# Haptic.net
KiCad netlist of a schematic drawn in EAGLE
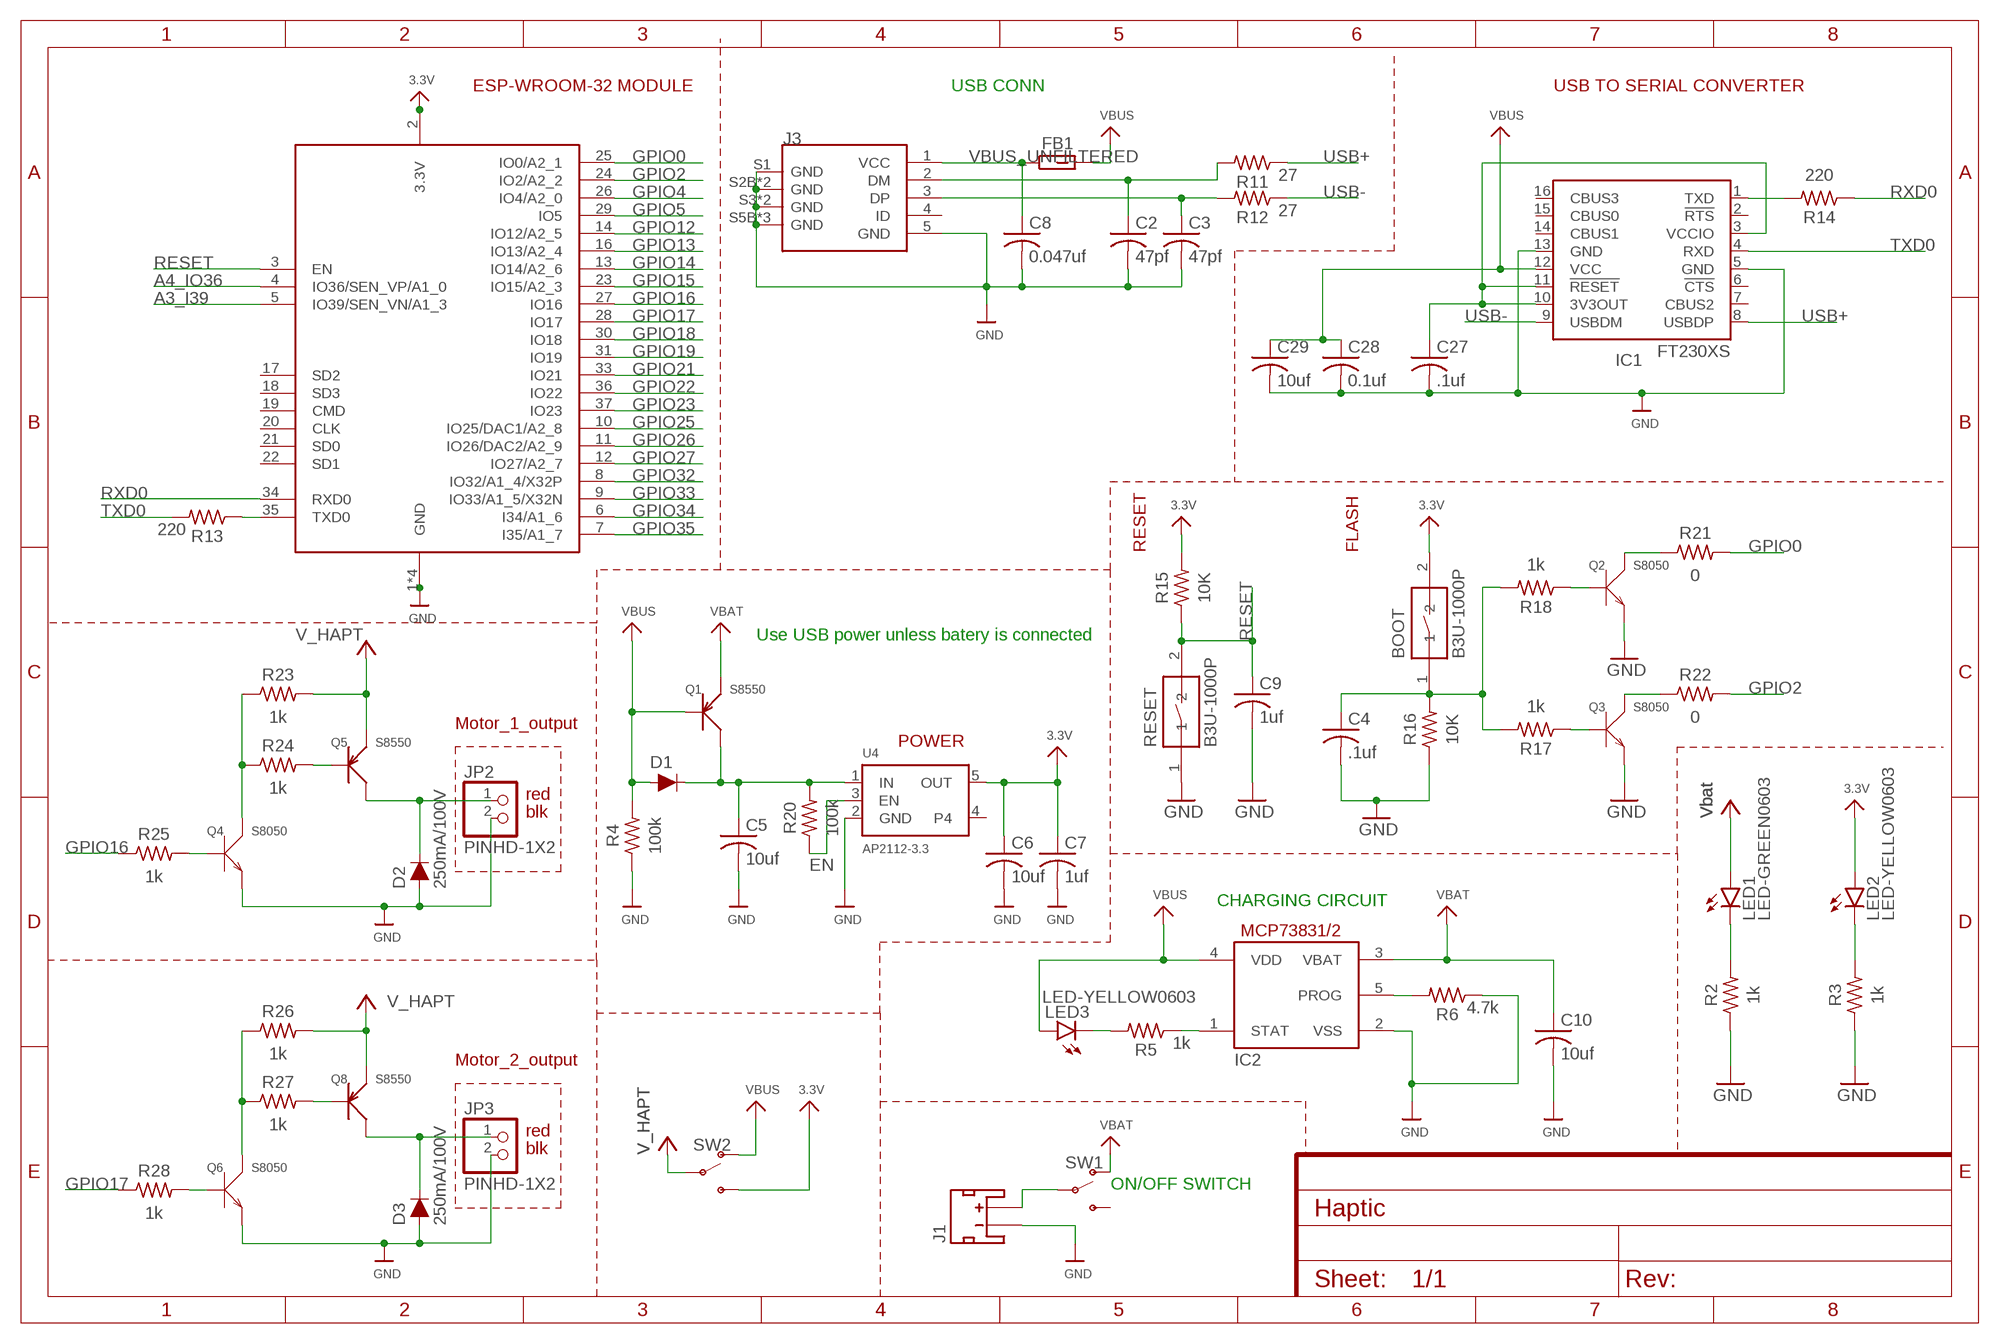
[diagram p0: schematic, sheet 1]

(export (version "E")
  (design (tool "Eeschema 10.0.6"))
  (components
    (comp (ref "BOOT")
      (value "B3U-1000P")
      (footprint "eagle-import:B3U-1000P")
      (fields
        (field (name "DIGI_KEY_PART_NUMBER") "SW1020CT-ND")
        (field (name "MANUFACTURER") "Omron Electronics Inc-EMC Div")
        (field (name "CREATED_BY") "PCBLayout.com")
      )
      (libsource (lib "eagle-import") (part "B3U-1000P"))
    )
    (comp (ref "C2")
      (value "47pf")
      (footprint "eagle-import:CAPC1608X85")
      (libsource (lib "eagle-import") (part "C-USCHIP-0603(1608-METRIC)_"))
    )
    (comp (ref "C3")
      (value "47pf")
      (footprint "eagle-import:CAPC1608X85")
      (libsource (lib "eagle-import") (part "C-USCHIP-0603(1608-METRIC)_"))
    )
    (comp (ref "C4")
      (value ".1uf")
      (footprint "eagle-import:CAPC1608X85")
      (libsource (lib "eagle-import") (part "C-USCHIP-0603(1608-METRIC)_"))
    )
    (comp (ref "C5")
      (value "10uf")
      (footprint "eagle-import:CAPC1608X85")
      (libsource (lib "eagle-import") (part "C-USCHIP-0603(1608-METRIC)_"))
    )
    (comp (ref "C6")
      (value "10uf")
      (footprint "eagle-import:CAPC1608X85")
      (libsource (lib "eagle-import") (part "C-USCHIP-0603(1608-METRIC)_"))
    )
    (comp (ref "C7")
      (value "1uf")
      (footprint "eagle-import:CAPC1608X85")
      (libsource (lib "eagle-import") (part "C-USCHIP-0603(1608-METRIC)_"))
    )
    (comp (ref "C8")
      (value "0.047uf")
      (footprint "eagle-import:CAPC1608X85")
      (libsource (lib "eagle-import") (part "C-USCHIP-0603(1608-METRIC)_"))
    )
    (comp (ref "C9")
      (value "1uf")
      (footprint "eagle-import:CAPC1608X85")
      (libsource (lib "eagle-import") (part "C-USCHIP-0603(1608-METRIC)_"))
    )
    (comp (ref "C10")
      (value "10uf")
      (footprint "eagle-import:CAPC1608X85")
      (libsource (lib "eagle-import") (part "C-USCHIP-0603(1608-METRIC)_"))
    )
    (comp (ref "C27")
      (value ".1uf")
      (footprint "eagle-import:CAPC1608X85")
      (libsource (lib "eagle-import") (part "C-USCHIP-0603(1608-METRIC)_"))
    )
    (comp (ref "C28")
      (value "0.1uf")
      (footprint "eagle-import:CAPC1608X85")
      (libsource (lib "eagle-import") (part "C-USCHIP-0603(1608-METRIC)_"))
    )
    (comp (ref "C29")
      (value "10uf")
      (footprint "eagle-import:CAPC1608X85")
      (libsource (lib "eagle-import") (part "C-USCHIP-0603(1608-METRIC)_"))
    )
    (comp (ref "D1")
      (value "250mA/100V")
      (footprint "eagle-import:SOD-323")
      (libsource (lib "eagle-import") (part "DIODE-BAS16J"))
    )
    (comp (ref "D2")
      (value "250mA/100V")
      (footprint "eagle-import:SOD-323")
      (libsource (lib "eagle-import") (part "DIODE-BAS16J"))
    )
    (comp (ref "D3")
      (value "250mA/100V")
      (footprint "eagle-import:SOD-323")
      (libsource (lib "eagle-import") (part "DIODE-BAS16J"))
    )
    (comp (ref "FB1")
      (value "BK1608TS601-T")
      (footprint "eagle-import:BEADC1608X95N")
      (libsource (lib "eagle-import") (part "FBCHIP-0603(1608-METRIC)"))
    )
    (comp (ref "IC1")
      (value "FT230XS")
      (footprint "eagle-import:SSOP16")
      (libsource (lib "eagle-import") (part "FT230XS"))
    )
    (comp (ref "IC2")
      (value "MCP73831/OT")
      (footprint "eagle-import:SOT23-5L")
      (libsource (lib "eagle-import") (part "MCP73831/OT"))
    )
    (comp (ref "J1")
      (value "JST_2MM_MALE")
      (footprint "eagle-import:JST-2-SMD")
      (libsource (lib "eagle-import") (part "JST_2MM_MALE"))
    )
    (comp (ref "J3")
      (value "10118193-0001LF")
      (footprint "eagle-import:MICRO-USB5+6P-SMD-0.65-B")
      (libsource (lib "eagle-import") (part "MICRO-USB-SMD-B-(10118193-0001LF)"))
    )
    (comp (ref "JP2")
      (value "PINHD-1X2")
      (footprint "eagle-import:1X02")
      (libsource (lib "eagle-import") (part "PINHD-1X2"))
    )
    (comp (ref "JP3")
      (value "PINHD-1X2")
      (footprint "eagle-import:1X02")
      (libsource (lib "eagle-import") (part "PINHD-1X2"))
    )
    (comp (ref "LED1")
      (value "LED-GREEN0603")
      (footprint "eagle-import:0603-GREEN")
      (libsource (lib "eagle-import") (part "LED-GREEN0603"))
    )
    (comp (ref "LED2")
      (value "LED-YELLOW0603")
      (footprint "eagle-import:0603-YELLOW")
      (libsource (lib "eagle-import") (part "LED-YELLOW0603"))
    )
    (comp (ref "LED3")
      (value "LED-YELLOW0603")
      (footprint "eagle-import:0603-YELLOW")
      (libsource (lib "eagle-import") (part "LED-YELLOW0603"))
    )
    (comp (ref "Q1")
      (value "S8550")
      (footprint "eagle-import:SOT-23")
      (libsource (lib "eagle-import") (part "SMD-TRANSISTORS-PNP-25V-500MA-S8550(SOT-23)"))
    )
    (comp (ref "Q2")
      (value "S8050")
      (footprint "eagle-import:SOT-23")
      (libsource (lib "eagle-import") (part "SMD-TRANSISTORS-NPN-25V-500MW-S8050(SOT-23)"))
    )
    (comp (ref "Q3")
      (value "S8050")
      (footprint "eagle-import:SOT-23")
      (libsource (lib "eagle-import") (part "SMD-TRANSISTORS-NPN-25V-500MW-S8050(SOT-23)"))
    )
    (comp (ref "Q4")
      (value "S8050")
      (footprint "eagle-import:SOT-23")
      (libsource (lib "eagle-import") (part "SMD-TRANSISTORS-NPN-25V-500MW-S8050(SOT-23)"))
    )
    (comp (ref "Q5")
      (value "S8550")
      (footprint "eagle-import:SOT-23")
      (libsource (lib "eagle-import") (part "SMD-TRANSISTORS-PNP-25V-500MA-S8550(SOT-23)"))
    )
    (comp (ref "Q6")
      (value "S8050")
      (footprint "eagle-import:SOT-23")
      (libsource (lib "eagle-import") (part "SMD-TRANSISTORS-NPN-25V-500MW-S8050(SOT-23)"))
    )
    (comp (ref "Q8")
      (value "S8550")
      (footprint "eagle-import:SOT-23")
      (libsource (lib "eagle-import") (part "SMD-TRANSISTORS-PNP-25V-500MA-S8550(SOT-23)"))
    )
    (comp (ref "R2")
      (value "1k")
      (footprint "eagle-import:RESC1608X60")
      (libsource (lib "eagle-import") (part "R-USCHIP-0603(1608-METRIC)_"))
    )
    (comp (ref "R3")
      (value "1k")
      (footprint "eagle-import:RESC1608X60")
      (libsource (lib "eagle-import") (part "R-USCHIP-0603(1608-METRIC)_"))
    )
    (comp (ref "R4")
      (value "100k")
      (footprint "eagle-import:RESC1608X60")
      (libsource (lib "eagle-import") (part "R-USCHIP-0603(1608-METRIC)_"))
    )
    (comp (ref "R5")
      (value "1k")
      (footprint "eagle-import:RESC1608X60")
      (libsource (lib "eagle-import") (part "R-USCHIP-0603(1608-METRIC)_"))
    )
    (comp (ref "R6")
      (value "4.7k")
      (footprint "eagle-import:RESC1608X60")
      (libsource (lib "eagle-import") (part "R-USCHIP-0603(1608-METRIC)_"))
    )
    (comp (ref "R11")
      (value "27")
      (footprint "eagle-import:RESC1608X60")
      (libsource (lib "eagle-import") (part "R-USCHIP-0603(1608-METRIC)_"))
    )
    (comp (ref "R12")
      (value "27")
      (footprint "eagle-import:RESC1608X60")
      (libsource (lib "eagle-import") (part "R-USCHIP-0603(1608-METRIC)_"))
    )
    (comp (ref "R13")
      (value "220")
      (footprint "eagle-import:RESC1608X60")
      (libsource (lib "eagle-import") (part "R-USCHIP-0603(1608-METRIC)_"))
    )
    (comp (ref "R14")
      (value "220")
      (footprint "eagle-import:RESC1608X60")
      (libsource (lib "eagle-import") (part "R-USCHIP-0603(1608-METRIC)_"))
    )
    (comp (ref "R15")
      (value "10K")
      (footprint "eagle-import:RESC1608X60")
      (libsource (lib "eagle-import") (part "R-USCHIP-0603(1608-METRIC)_"))
    )
    (comp (ref "R16")
      (value "10K")
      (footprint "eagle-import:RESC1608X60")
      (libsource (lib "eagle-import") (part "R-USCHIP-0603(1608-METRIC)_"))
    )
    (comp (ref "R17")
      (value "1k")
      (footprint "eagle-import:RESC1608X60")
      (libsource (lib "eagle-import") (part "R-USCHIP-0603(1608-METRIC)_"))
    )
    (comp (ref "R18")
      (value "1k")
      (footprint "eagle-import:RESC1608X60")
      (libsource (lib "eagle-import") (part "R-USCHIP-0603(1608-METRIC)_"))
    )
    (comp (ref "R20")
      (value "100k")
      (footprint "eagle-import:RESC1608X60")
      (libsource (lib "eagle-import") (part "R-USCHIP-0603(1608-METRIC)_"))
    )
    (comp (ref "R21")
      (value "0")
      (footprint "eagle-import:RESC1608X60")
      (libsource (lib "eagle-import") (part "R-USCHIP-0603(1608-METRIC)_"))
    )
    (comp (ref "R22")
      (value "0")
      (footprint "eagle-import:RESC1608X60")
      (libsource (lib "eagle-import") (part "R-USCHIP-0603(1608-METRIC)_"))
    )
    (comp (ref "R23")
      (value "1k")
      (footprint "eagle-import:RESC1608X60")
      (libsource (lib "eagle-import") (part "R-USCHIP-0603(1608-METRIC)_"))
    )
    (comp (ref "R24")
      (value "1k")
      (footprint "eagle-import:RESC1608X60")
      (libsource (lib "eagle-import") (part "R-USCHIP-0603(1608-METRIC)_"))
    )
    (comp (ref "R25")
      (value "1k")
      (footprint "eagle-import:RESC1608X60")
      (libsource (lib "eagle-import") (part "R-USCHIP-0603(1608-METRIC)_"))
    )
    (comp (ref "R26")
      (value "1k")
      (footprint "eagle-import:RESC1608X60")
      (libsource (lib "eagle-import") (part "R-USCHIP-0603(1608-METRIC)_"))
    )
    (comp (ref "R27")
      (value "1k")
      (footprint "eagle-import:RESC1608X60")
      (libsource (lib "eagle-import") (part "R-USCHIP-0603(1608-METRIC)_"))
    )
    (comp (ref "R28")
      (value "1k")
      (footprint "eagle-import:RESC1608X60")
      (libsource (lib "eagle-import") (part "R-USCHIP-0603(1608-METRIC)_"))
    )
    (comp (ref "RESET")
      (value "B3U-1000P")
      (footprint "eagle-import:B3U-1000P")
      (fields
        (field (name "DIGI_KEY_PART_NUMBER") "SW1020CT-ND")
        (field (name "MANUFACTURER") "Omron Electronics Inc-EMC Div")
        (field (name "CREATED_BY") "PCBLayout.com")
      )
      (libsource (lib "eagle-import") (part "B3U-1000P"))
    )
    (comp (ref "SW1")
      (value "SWITCH-SPDT-SMD-RIGHT-ANGLE")
      (footprint "eagle-import:SWITCH_SPST_SMD_A")
      (libsource (lib "eagle-import") (part "SWITCH-SPDT-SMD-RIGHT-ANGLE"))
    )
    (comp (ref "SW2")
      (value "SWITCH-SPDT-SMD-RIGHT-ANGLE")
      (footprint "eagle-import:SWITCH_SPST_SMD_A")
      (libsource (lib "eagle-import") (part "SWITCH-SPDT-SMD-RIGHT-ANGLE"))
    )
    (comp (ref "U4")
      (value "AP2112-3.3")
      (footprint "eagle-import:SOT23-5")
      (libsource (lib "eagle-import") (part "VREG_SOT23-5"))
    )
    (comp (ref "X6")
      (value "ESP32_WROOM32_SKINNY")
      (footprint "eagle-import:WROOM32_SKINNY")
      (libsource (lib "eagle-import") (part "ESP32_WROOM32_SKINNY"))
    )
  )
  (nets
    (net (code "1") (name "/A3_I39") (class "Default")
      (node (ref "X6") (pin "5") (pinfunction "IO39/SEN_VN/A1_3_5") (pintype "passive"))
    )
    (net (code "2") (name "/A4_IO36") (class "Default")
      (node (ref "X6") (pin "4") (pinfunction "IO36/SEN_VP/A1_0_4") (pintype "passive"))
    )
    (net (code "3") (name "/EN") (class "Default")
      (node (ref "R20") (pin "1") (pinfunction "1_1") (pintype "passive"))
      (node (ref "U4") (pin "3") (pinfunction "EN_3") (pintype "input"))
    )
    (net (code "4") (name "/GPIO0") (class "Default")
      (node (ref "R21") (pin "2") (pinfunction "2_2") (pintype "passive"))
      (node (ref "X6") (pin "25") (pinfunction "IO0/A2_1_25") (pintype "bidirectional"))
    )
    (net (code "5") (name "/GPIO2") (class "Default")
      (node (ref "R22") (pin "2") (pinfunction "2_2") (pintype "passive"))
      (node (ref "X6") (pin "24") (pinfunction "IO2/A2_2_24") (pintype "bidirectional"))
    )
    (net (code "6") (name "/GPIO4") (class "Default")
      (node (ref "X6") (pin "26") (pinfunction "IO4/A2_0_26") (pintype "bidirectional"))
    )
    (net (code "7") (name "/GPIO5") (class "Default")
      (node (ref "X6") (pin "29") (pinfunction "IO5_29") (pintype "bidirectional"))
    )
    (net (code "8") (name "/GPIO12") (class "Default")
      (node (ref "X6") (pin "14") (pinfunction "IO12/A2_5_14") (pintype "bidirectional"))
    )
    (net (code "9") (name "/GPIO13") (class "Default")
      (node (ref "X6") (pin "16") (pinfunction "IO13/A2_4_16") (pintype "bidirectional"))
    )
    (net (code "10") (name "/GPIO14") (class "Default")
      (node (ref "X6") (pin "13") (pinfunction "IO14/A2_6_13") (pintype "bidirectional"))
    )
    (net (code "11") (name "/GPIO15") (class "Default")
      (node (ref "X6") (pin "23") (pinfunction "IO15/A2_3_23") (pintype "bidirectional"))
    )
    (net (code "12") (name "/GPIO16") (class "Default")
      (node (ref "R25") (pin "1") (pinfunction "1_1") (pintype "passive"))
      (node (ref "X6") (pin "27") (pinfunction "IO16_27") (pintype "bidirectional"))
    )
    (net (code "13") (name "/GPIO17") (class "Default")
      (node (ref "R28") (pin "1") (pinfunction "1_1") (pintype "passive"))
      (node (ref "X6") (pin "28") (pinfunction "IO17_28") (pintype "bidirectional"))
    )
    (net (code "14") (name "/GPIO18") (class "Default")
      (node (ref "X6") (pin "30") (pinfunction "IO18_30") (pintype "bidirectional"))
    )
    (net (code "15") (name "/GPIO19") (class "Default")
      (node (ref "X6") (pin "31") (pinfunction "IO19_31") (pintype "bidirectional"))
    )
    (net (code "16") (name "/GPIO21") (class "Default")
      (node (ref "X6") (pin "33") (pinfunction "IO21_33") (pintype "bidirectional"))
    )
    (net (code "17") (name "/GPIO22") (class "Default")
      (node (ref "X6") (pin "36") (pinfunction "IO22_36") (pintype "bidirectional"))
    )
    (net (code "18") (name "/GPIO23") (class "Default")
      (node (ref "X6") (pin "37") (pinfunction "IO23_37") (pintype "bidirectional"))
    )
    (net (code "19") (name "/GPIO25") (class "Default")
      (node (ref "X6") (pin "10") (pinfunction "IO25/DAC1/A2_8_10") (pintype "bidirectional"))
    )
    (net (code "20") (name "/GPIO26") (class "Default")
      (node (ref "X6") (pin "11") (pinfunction "IO26/DAC2/A2_9_11") (pintype "bidirectional"))
    )
    (net (code "21") (name "/GPIO27") (class "Default")
      (node (ref "X6") (pin "12") (pinfunction "IO27/A2_7_12") (pintype "bidirectional"))
    )
    (net (code "22") (name "/GPIO32") (class "Default")
      (node (ref "X6") (pin "8") (pinfunction "IO32/A1_4/X32P_8") (pintype "bidirectional"))
    )
    (net (code "23") (name "/GPIO33") (class "Default")
      (node (ref "X6") (pin "9") (pinfunction "IO33/A1_5/X32N_9") (pintype "bidirectional"))
    )
    (net (code "24") (name "/GPIO34") (class "Default")
      (node (ref "X6") (pin "6") (pinfunction "I34/A1_6_6") (pintype "bidirectional"))
    )
    (net (code "25") (name "/GPIO35") (class "Default")
      (node (ref "X6") (pin "7") (pinfunction "I35/A1_7_7") (pintype "bidirectional"))
    )
    (net (code "26") (name "/RESET") (class "Default")
      (node (ref "C9") (pin "1") (pinfunction "1_1") (pintype "passive"))
      (node (ref "R15") (pin "1") (pinfunction "1_1") (pintype "passive"))
      (node (ref "RESET") (pin "2") (pinfunction "2_2") (pintype "passive"))
      (node (ref "X6") (pin "3") (pinfunction "EN_3") (pintype "input"))
    )
    (net (code "27") (name "/RXD0") (class "Default")
      (node (ref "R14") (pin "1") (pinfunction "1_1") (pintype "passive"))
      (node (ref "X6") (pin "34") (pinfunction "RXD0_34") (pintype "input"))
    )
    (net (code "28") (name "/TXD0") (class "Default")
      (node (ref "IC1") (pin "4") (pinfunction "RXD_4") (pintype "input"))
      (node (ref "R13") (pin "2") (pinfunction "2_2") (pintype "passive"))
    )
    (net (code "29") (name "/USB+") (class "Default")
      (node (ref "IC1") (pin "8") (pinfunction "USBDP_8") (pintype "input"))
      (node (ref "R12") (pin "1") (pinfunction "1_1") (pintype "passive"))
    )
    (net (code "30") (name "/USB-") (class "Default")
      (node (ref "IC1") (pin "9") (pinfunction "USBDM_9") (pintype "input"))
      (node (ref "R11") (pin "1") (pinfunction "1_1") (pintype "passive"))
    )
    (net (code "31") (name "/VBUS_UNFILTERED") (class "Default")
      (node (ref "C8") (pin "1") (pinfunction "1_1") (pintype "passive"))
      (node (ref "FB1") (pin "1") (pinfunction "1_1") (pintype "passive"))
      (node (ref "J3") (pin "1") (pinfunction "VCC_1") (pintype "bidirectional"))
    )
    (net (code "32") (name "3.3V") (class "Default")
      (node (ref "BOOT") (pin "2") (pinfunction "2_2") (pintype "passive"))
      (node (ref "C6") (pin "1") (pinfunction "1_1") (pintype "passive"))
      (node (ref "C7") (pin "1") (pinfunction "1_1") (pintype "passive"))
      (node (ref "LED2") (pin "A") (pinfunction "A_A") (pintype "passive"))
      (node (ref "R15") (pin "2") (pinfunction "2_2") (pintype "passive"))
      (node (ref "SW2") (pin "3") (pinfunction "S_3") (pintype "passive"))
      (node (ref "U4") (pin "5") (pinfunction "OUT_5") (pintype "power_in"))
      (node (ref "X6") (pin "2") (pinfunction "3.3V_2") (pintype "passive"))
    )
    (net (code "33") (name "GND") (class "Default")
      (node (ref "C10") (pin "2") (pinfunction "2_2") (pintype "passive"))
      (node (ref "C2") (pin "2") (pinfunction "2_2") (pintype "passive"))
      (node (ref "C27") (pin "2") (pinfunction "2_2") (pintype "passive"))
      (node (ref "C28") (pin "2") (pinfunction "2_2") (pintype "passive"))
      (node (ref "C29") (pin "2") (pinfunction "2_2") (pintype "passive"))
      (node (ref "C3") (pin "2") (pinfunction "2_2") (pintype "passive"))
      (node (ref "C4") (pin "2") (pinfunction "2_2") (pintype "passive"))
      (node (ref "C5") (pin "2") (pinfunction "2_2") (pintype "passive"))
      (node (ref "C6") (pin "2") (pinfunction "2_2") (pintype "passive"))
      (node (ref "C7") (pin "2") (pinfunction "2_2") (pintype "passive"))
      (node (ref "C8") (pin "2") (pinfunction "2_2") (pintype "passive"))
      (node (ref "C9") (pin "2") (pinfunction "2_2") (pintype "passive"))
      (node (ref "D2") (pin "A") (pinfunction "A_A") (pintype "passive"))
      (node (ref "D3") (pin "A") (pinfunction "A_A") (pintype "passive"))
      (node (ref "IC1") (pin "13") (pinfunction "GND_13") (pintype "power_in"))
      (node (ref "IC1") (pin "5") (pinfunction "GND_5") (pintype "power_in"))
      (node (ref "IC2") (pin "2") (pinfunction "VSS_2") (pintype "power_in"))
      (node (ref "J1") (pin "1") (pinfunction "-_1") (pintype "bidirectional"))
      (node (ref "J3") (pin "5") (pinfunction "GND_5") (pintype "bidirectional"))
      (node (ref "J3") (pin "S1") (pinfunction "GND_S1") (pintype "bidirectional"))
      (node (ref "J3") (pin "S2B") (pinfunction "GND_S2B") (pintype "bidirectional"))
      (node (ref "J3") (pin "S2T") (pinfunction "GND_S2T") (pintype "bidirectional"))
      (node (ref "J3") (pin "S3") (pinfunction "GND_S3") (pintype "bidirectional"))
      (node (ref "J3") (pin "S4") (pinfunction "GND_S4") (pintype "bidirectional"))
      (node (ref "J3") (pin "S5B") (pinfunction "GND_S5B") (pintype "bidirectional"))
      (node (ref "J3") (pin "S5T") (pinfunction "GND_S5T") (pintype "bidirectional"))
      (node (ref "J3") (pin "S6") (pinfunction "GND_S6") (pintype "bidirectional"))
      (node (ref "JP2") (pin "2") (pinfunction "2_2") (pintype "passive"))
      (node (ref "JP3") (pin "2") (pinfunction "2_2") (pintype "passive"))
      (node (ref "Q2") (pin "2") (pinfunction "E_2") (pintype "passive"))
      (node (ref "Q3") (pin "2") (pinfunction "E_2") (pintype "passive"))
      (node (ref "Q4") (pin "2") (pinfunction "E_2") (pintype "passive"))
      (node (ref "Q6") (pin "2") (pinfunction "E_2") (pintype "passive"))
      (node (ref "R16") (pin "1") (pinfunction "1_1") (pintype "passive"))
      (node (ref "R2") (pin "1") (pinfunction "1_1") (pintype "passive"))
      (node (ref "R3") (pin "1") (pinfunction "1_1") (pintype "passive"))
      (node (ref "R4") (pin "1") (pinfunction "1_1") (pintype "passive"))
      (node (ref "R6") (pin "1") (pinfunction "1_1") (pintype "passive"))
      (node (ref "RESET") (pin "1") (pinfunction "1_1") (pintype "passive"))
      (node (ref "U4") (pin "2") (pinfunction "GND_2") (pintype "power_in"))
      (node (ref "X6") (pin "1") (pinfunction "GND_1") (pintype "passive"))
      (node (ref "X6") (pin "15") (pinfunction "GND_15") (pintype "passive"))
      (node (ref "X6") (pin "38") (pinfunction "GND_38") (pintype "passive"))
      (node (ref "X6") (pin "P$1") (pinfunction "GND_P$1") (pintype "passive"))
    )
    (net (code "34") (name "Net-(BOOT-Pad1)") (class "Default")
      (node (ref "BOOT") (pin "1") (pinfunction "1_1") (pintype "passive"))
      (node (ref "C4") (pin "1") (pinfunction "1_1") (pintype "passive"))
      (node (ref "R16") (pin "2") (pinfunction "2_2") (pintype "passive"))
      (node (ref "R17") (pin "2") (pinfunction "2_2") (pintype "passive"))
      (node (ref "R18") (pin "2") (pinfunction "2_2") (pintype "passive"))
    )
    (net (code "35") (name "Net-(IC1-3V3OUT)") (class "Default")
      (node (ref "C27") (pin "1") (pinfunction "1_1") (pintype "passive"))
      (node (ref "IC1") (pin "10") (pinfunction "3V3OUT_10") (pintype "output"))
      (node (ref "IC1") (pin "11") (pinfunction "~{RESET}_11") (pintype "input"))
      (node (ref "IC1") (pin "3") (pinfunction "VCCIO_3") (pintype "power_in"))
    )
    (net (code "36") (name "Net-(IC1-TXD)") (class "Default")
      (node (ref "IC1") (pin "1") (pinfunction "TXD_1") (pintype "output"))
      (node (ref "R14") (pin "2") (pinfunction "2_2") (pintype "passive"))
    )
    (net (code "37") (name "Net-(IC2-PROG)") (class "Default")
      (node (ref "IC2") (pin "5") (pinfunction "PROG_5") (pintype "input"))
      (node (ref "R6") (pin "2") (pinfunction "2_2") (pintype "passive"))
    )
    (net (code "38") (name "Net-(IC2-STAT)") (class "Default")
      (node (ref "IC2") (pin "1") (pinfunction "STAT_1") (pintype "output"))
      (node (ref "R5") (pin "1") (pinfunction "1_1") (pintype "passive"))
    )
    (net (code "39") (name "Net-(J1-+)") (class "Default")
      (node (ref "J1") (pin "2") (pinfunction "+_2") (pintype "bidirectional"))
      (node (ref "SW1") (pin "2") (pinfunction "P_2") (pintype "passive"))
    )
    (net (code "40") (name "Net-(J3-DM)") (class "Default")
      (node (ref "C2") (pin "1") (pinfunction "1_1") (pintype "passive"))
      (node (ref "J3") (pin "2") (pinfunction "DM_2") (pintype "bidirectional"))
      (node (ref "R11") (pin "2") (pinfunction "2_2") (pintype "passive"))
    )
    (net (code "41") (name "Net-(J3-DP)") (class "Default")
      (node (ref "C3") (pin "1") (pinfunction "1_1") (pintype "passive"))
      (node (ref "J3") (pin "3") (pinfunction "DP_3") (pintype "bidirectional"))
      (node (ref "R12") (pin "2") (pinfunction "2_2") (pintype "passive"))
    )
    (net (code "42") (name "Net-(LED1-PadC)") (class "Default")
      (node (ref "LED1") (pin "C") (pinfunction "C_C") (pintype "passive"))
      (node (ref "R2") (pin "2") (pinfunction "2_2") (pintype "passive"))
    )
    (net (code "43") (name "Net-(LED2-PadC)") (class "Default")
      (node (ref "LED2") (pin "C") (pinfunction "C_C") (pintype "passive"))
      (node (ref "R3") (pin "2") (pinfunction "2_2") (pintype "passive"))
    )
    (net (code "44") (name "Net-(LED3-PadC)") (class "Default")
      (node (ref "LED3") (pin "C") (pinfunction "C_C") (pintype "passive"))
      (node (ref "R5") (pin "2") (pinfunction "2_2") (pintype "passive"))
    )
    (net (code "45") (name "Net-(Q1-C)") (class "Default")
      (node (ref "C5") (pin "1") (pinfunction "1_1") (pintype "passive"))
      (node (ref "D1") (pin "C") (pinfunction "C_C") (pintype "passive"))
      (node (ref "Q1") (pin "3") (pinfunction "C_3") (pintype "passive"))
      (node (ref "R20") (pin "2") (pinfunction "2_2") (pintype "passive"))
      (node (ref "U4") (pin "1") (pinfunction "IN_1") (pintype "power_in"))
    )
    (net (code "46") (name "Net-(Q2-B)") (class "Default")
      (node (ref "Q2") (pin "1") (pinfunction "B_1") (pintype "passive"))
      (node (ref "R18") (pin "1") (pinfunction "1_1") (pintype "passive"))
    )
    (net (code "47") (name "Net-(Q2-C)") (class "Default")
      (node (ref "Q2") (pin "3") (pinfunction "C_3") (pintype "passive"))
      (node (ref "R21") (pin "1") (pinfunction "1_1") (pintype "passive"))
    )
    (net (code "48") (name "Net-(Q3-B)") (class "Default")
      (node (ref "Q3") (pin "1") (pinfunction "B_1") (pintype "passive"))
      (node (ref "R17") (pin "1") (pinfunction "1_1") (pintype "passive"))
    )
    (net (code "49") (name "Net-(Q3-C)") (class "Default")
      (node (ref "Q3") (pin "3") (pinfunction "C_3") (pintype "passive"))
      (node (ref "R22") (pin "1") (pinfunction "1_1") (pintype "passive"))
    )
    (net (code "50") (name "Net-(Q4-B)") (class "Default")
      (node (ref "Q4") (pin "1") (pinfunction "B_1") (pintype "passive"))
      (node (ref "R25") (pin "2") (pinfunction "2_2") (pintype "passive"))
    )
    (net (code "51") (name "Net-(Q4-C)") (class "Default")
      (node (ref "Q4") (pin "3") (pinfunction "C_3") (pintype "passive"))
      (node (ref "R23") (pin "1") (pinfunction "1_1") (pintype "passive"))
      (node (ref "R24") (pin "1") (pinfunction "1_1") (pintype "passive"))
    )
    (net (code "52") (name "Net-(Q5-B)") (class "Default")
      (node (ref "Q5") (pin "1") (pinfunction "B_1") (pintype "passive"))
      (node (ref "R24") (pin "2") (pinfunction "2_2") (pintype "passive"))
    )
    (net (code "53") (name "Net-(Q5-C)") (class "Default")
      (node (ref "D2") (pin "C") (pinfunction "C_C") (pintype "passive"))
      (node (ref "JP2") (pin "1") (pinfunction "1_1") (pintype "passive"))
      (node (ref "Q5") (pin "3") (pinfunction "C_3") (pintype "passive"))
    )
    (net (code "54") (name "Net-(Q6-B)") (class "Default")
      (node (ref "Q6") (pin "1") (pinfunction "B_1") (pintype "passive"))
      (node (ref "R28") (pin "2") (pinfunction "2_2") (pintype "passive"))
    )
    (net (code "55") (name "Net-(Q6-C)") (class "Default")
      (node (ref "Q6") (pin "3") (pinfunction "C_3") (pintype "passive"))
      (node (ref "R26") (pin "1") (pinfunction "1_1") (pintype "passive"))
      (node (ref "R27") (pin "1") (pinfunction "1_1") (pintype "passive"))
    )
    (net (code "56") (name "Net-(Q8-B)") (class "Default")
      (node (ref "Q8") (pin "1") (pinfunction "B_1") (pintype "passive"))
      (node (ref "R27") (pin "2") (pinfunction "2_2") (pintype "passive"))
    )
    (net (code "57") (name "Net-(Q8-C)") (class "Default")
      (node (ref "D3") (pin "C") (pinfunction "C_C") (pintype "passive"))
      (node (ref "JP3") (pin "1") (pinfunction "1_1") (pintype "passive"))
      (node (ref "Q8") (pin "3") (pinfunction "C_3") (pintype "passive"))
    )
    (net (code "58") (name "Net-(X6-TXD0)") (class "Default")
      (node (ref "R13") (pin "1") (pinfunction "1_1") (pintype "passive"))
      (node (ref "X6") (pin "35") (pinfunction "TXD0_35") (pintype "output"))
    )
    (net (code "59") (name "VBAT") (class "Default")
      (node (ref "C10") (pin "1") (pinfunction "1_1") (pintype "passive"))
      (node (ref "IC2") (pin "3") (pinfunction "VBAT_3") (pintype "bidirectional"))
      (node (ref "Q1") (pin "2") (pinfunction "E_2") (pintype "passive"))
      (node (ref "SW1") (pin "1") (pinfunction "O_1") (pintype "passive"))
    )
    (net (code "60") (name "VBUS") (class "Default")
      (node (ref "C28") (pin "1") (pinfunction "1_1") (pintype "passive"))
      (node (ref "C29") (pin "1") (pinfunction "1_1") (pintype "passive"))
      (node (ref "D1") (pin "A") (pinfunction "A_A") (pintype "passive"))
      (node (ref "FB1") (pin "2") (pinfunction "2_2") (pintype "passive"))
      (node (ref "IC1") (pin "12") (pinfunction "VCC_12") (pintype "power_in"))
      (node (ref "IC2") (pin "4") (pinfunction "VDD_4") (pintype "power_in"))
      (node (ref "LED3") (pin "A") (pinfunction "A_A") (pintype "passive"))
      (node (ref "Q1") (pin "1") (pinfunction "B_1") (pintype "passive"))
      (node (ref "R4") (pin "2") (pinfunction "2_2") (pintype "passive"))
      (node (ref "SW2") (pin "1") (pinfunction "O_1") (pintype "passive"))
    )
    (net (code "61") (name "V_HAPT") (class "Default")
      (node (ref "LED1") (pin "A") (pinfunction "A_A") (pintype "passive"))
      (node (ref "Q5") (pin "2") (pinfunction "E_2") (pintype "passive"))
      (node (ref "Q8") (pin "2") (pinfunction "E_2") (pintype "passive"))
      (node (ref "R23") (pin "2") (pinfunction "2_2") (pintype "passive"))
      (node (ref "R26") (pin "2") (pinfunction "2_2") (pintype "passive"))
      (node (ref "SW2") (pin "2") (pinfunction "P_2") (pintype "passive"))
    )
    (net (code "62") (name "unconnected-(IC1-CBUS0-Pad15)") (class "Default")
      (node (ref "IC1") (pin "15") (pinfunction "CBUS0_15") (pintype "bidirectional"))
    )
    (net (code "63") (name "unconnected-(IC1-CBUS1-Pad14)") (class "Default")
      (node (ref "IC1") (pin "14") (pinfunction "CBUS1_14") (pintype "bidirectional"))
    )
    (net (code "64") (name "unconnected-(IC1-CBUS2-Pad7)") (class "Default")
      (node (ref "IC1") (pin "7") (pinfunction "CBUS2_7") (pintype "bidirectional"))
    )
    (net (code "65") (name "unconnected-(IC1-CBUS3-Pad16)") (class "Default")
      (node (ref "IC1") (pin "16") (pinfunction "CBUS3_16") (pintype "bidirectional"))
    )
    (net (code "66") (name "unconnected-(IC1-~{CTS}-Pad6)") (class "Default")
      (node (ref "IC1") (pin "6") (pinfunction "~{CTS}_6") (pintype "input"))
    )
    (net (code "67") (name "unconnected-(IC1-~{RTS}-Pad2)") (class "Default")
      (node (ref "IC1") (pin "2") (pinfunction "~{RTS}_2") (pintype "output"))
    )
    (net (code "68") (name "unconnected-(J1-PAD1-PadNC1)") (class "Default")
      (node (ref "J1") (pin "NC1") (pinfunction "PAD1_NC1") (pintype "bidirectional"))
    )
    (net (code "69") (name "unconnected-(J1-PAD2-PadNC2)") (class "Default")
      (node (ref "J1") (pin "NC2") (pinfunction "PAD2_NC2") (pintype "bidirectional"))
    )
    (net (code "70") (name "unconnected-(J3-ID-Pad4)") (class "Default")
      (node (ref "J3") (pin "4") (pinfunction "ID_4") (pintype "bidirectional"))
    )
    (net (code "71") (name "unconnected-(SW1-S-Pad3)") (class "Default")
      (node (ref "SW1") (pin "3") (pinfunction "S_3") (pintype "passive"))
    )
    (net (code "72") (name "unconnected-(U4-P4-Pad4)") (class "Default")
      (node (ref "U4") (pin "4") (pinfunction "P4_4") (pintype "bidirectional"))
    )
    (net (code "73") (name "unconnected-(X6-CLK-Pad20)") (class "Default")
      (node (ref "X6") (pin "20") (pinfunction "CLK_20") (pintype "bidirectional"))
    )
    (net (code "74") (name "unconnected-(X6-CMD-Pad19)") (class "Default")
      (node (ref "X6") (pin "19") (pinfunction "CMD_19") (pintype "bidirectional"))
    )
    (net (code "75") (name "unconnected-(X6-SD0-Pad21)") (class "Default")
      (node (ref "X6") (pin "21") (pinfunction "SD0_21") (pintype "bidirectional"))
    )
    (net (code "76") (name "unconnected-(X6-SD1-Pad22)") (class "Default")
      (node (ref "X6") (pin "22") (pinfunction "SD1_22") (pintype "bidirectional"))
    )
    (net (code "77") (name "unconnected-(X6-SD2-Pad17)") (class "Default")
      (node (ref "X6") (pin "17") (pinfunction "SD2_17") (pintype "bidirectional"))
    )
    (net (code "78") (name "unconnected-(X6-SD3-Pad18)") (class "Default")
      (node (ref "X6") (pin "18") (pinfunction "SD3_18") (pintype "bidirectional"))
    )
  )
)
